# imu.net
KiCad netlist of a schematic drawn in Altium Designer
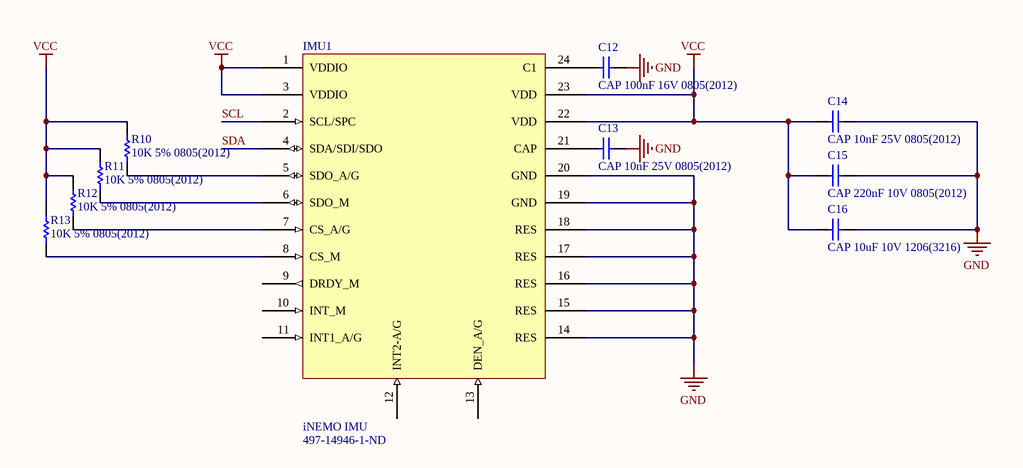
[diagram p0: imu.SchDoc]

(export (version "E")
  (design (tool "Eeschema 10.0.6"))
  (components
    (comp (ref "C12")
      (value "CAP 100nF 16V 0805(2012)")
      (footprint "CAPC0805(2012)145_M")
      (description "CAP 100nF 16V ±20% 0805 (2012 Metric) Thickness 1.45mm SMD")
      (fields (field (name "TOLERANCE") "Â±20%"))
      (libsource (lib "Altium Content Vault") (part "CAP"))
    )
    (comp (ref "C13")
      (value "CAP 10nF 25V 0805(2012)")
      (footprint "CAPC0805(2012)100_L")
      (description "CAP 10nF 25V ±2% 0805 (2012 Metric) Thickness 1mm SMD")
      (fields (field (name "TOLERANCE") "Â±2%"))
      (libsource (lib "Altium Content Vault") (part "CMP-1036-03826-1"))
    )
    (comp (ref "C14")
      (value "CAP 10nF 25V 0805(2012)")
      (footprint "CAPC0805(2012)100_L")
      (description "CAP 10nF 25V ±2% 0805 (2012 Metric) Thickness 1mm SMD")
      (fields (field (name "TOLERANCE") "Â±2%"))
      (libsource (lib "Altium Content Vault") (part "CMP-1036-03826-1"))
    )
    (comp (ref "C15")
      (value "CAP 220nF 10V 0805(2012)")
      (footprint "CAPC0805(2012)75_N")
      (description "CAP 220nF 10V ±20% 0805 (2012 Metric) Thickness 0.75mm SMD")
      (fields (field (name "TOLERANCE") "Â±20%"))
      (libsource (lib "Altium Content Vault") (part "CMP-1036-04526-1"))
    )
    (comp (ref "C16")
      (value "CAP 10uF 10V 1206(3216)")
      (footprint "CAPC1206(3216)130_L")
      (description "CAP 10uF 10V -20% to +80% 1206 (3216 Metric) Thickness 1.3mm SMD")
      (fields (field (name "TOLERANCE") "-20% to +80%"))
      (libsource (lib "Altium Content Vault") (part "CMP-1037-04970-1"))
    )
    (comp (ref "IMU1")
      (value "iNEMO IMU")
      (footprint "LGA-24")
      (fields (field (name "SUPPLIER PART NUMBER 1") "497-14946-1-ND"))
      (libsource (lib "lab4") (part "LSM9DS1"))
    )
    (comp (ref "R10")
      (value "10K 5% 0805(2012)")
      (footprint "RESC0805(2012)_L")
      (description "10K 0.125W 5% 0805 (2012 Metric)  SMD")
      (fields (field (name "POWER") "0.125 W") (field (name "TOLERANCE") "5 %"))
      (libsource (lib "Altium Content Vault") (part "CMP-1013-00098-1"))
    )
    (comp (ref "R11")
      (value "10K 5% 0805(2012)")
      (footprint "RESC0805(2012)_L")
      (description "10K 0.125W 5% 0805 (2012 Metric)  SMD")
      (fields (field (name "POWER") "0.125 W") (field (name "TOLERANCE") "5 %"))
      (libsource (lib "Altium Content Vault") (part "CMP-1013-00098-1"))
    )
    (comp (ref "R12")
      (value "10K 5% 0805(2012)")
      (footprint "RESC0805(2012)_L")
      (description "10K 0.125W 5% 0805 (2012 Metric)  SMD")
      (fields (field (name "POWER") "0.125 W") (field (name "TOLERANCE") "5 %"))
      (libsource (lib "Altium Content Vault") (part "CMP-1013-00098-1"))
    )
    (comp (ref "R13")
      (value "10K 5% 0805(2012)")
      (footprint "RESC0805(2012)_L")
      (description "10K 0.125W 5% 0805 (2012 Metric)  SMD")
      (fields (field (name "POWER") "0.125 W") (field (name "TOLERANCE") "5 %"))
      (libsource (lib "Altium Content Vault") (part "CMP-1013-00098-1"))
    )
  )
  (nets
    (net (code "1") (name "/SCL") (class "Default")
      (node (ref "IMU1") (pin "2") (pinfunction "SCL/SPC_2") (pintype "input"))
    )
    (net (code "2") (name "/SDA") (class "Default")
      (node (ref "IMU1") (pin "4") (pinfunction "SDA/SDI/SDO_4") (pintype "bidirectional"))
    )
    (net (code "3") (name "GND") (class "Default")
      (node (ref "C12") (pin "2") (pinfunction "2_2") (pintype "passive"))
      (node (ref "C13") (pin "2") (pinfunction "2_2") (pintype "passive"))
      (node (ref "C14") (pin "2") (pinfunction "2_2") (pintype "passive"))
      (node (ref "C15") (pin "1") (pinfunction "1_1") (pintype "passive"))
      (node (ref "C16") (pin "2") (pinfunction "2_2") (pintype "passive"))
      (node (ref "IMU1") (pin "14") (pinfunction "RES_14") (pintype "passive"))
      (node (ref "IMU1") (pin "15") (pinfunction "RES_15") (pintype "passive"))
      (node (ref "IMU1") (pin "16") (pinfunction "RES_16") (pintype "passive"))
      (node (ref "IMU1") (pin "17") (pinfunction "RES_17") (pintype "passive"))
      (node (ref "IMU1") (pin "18") (pinfunction "RES_18") (pintype "passive"))
      (node (ref "IMU1") (pin "19") (pinfunction "GND_19") (pintype "power_in"))
      (node (ref "IMU1") (pin "20") (pinfunction "GND_20") (pintype "power_in"))
    )
    (net (code "4") (name "Net-(IMU1-C1)") (class "Default")
      (node (ref "C12") (pin "1") (pinfunction "1_1") (pintype "passive"))
      (node (ref "IMU1") (pin "24") (pinfunction "C1_24") (pintype "passive"))
    )
    (net (code "5") (name "Net-(IMU1-CAP)") (class "Default")
      (node (ref "C13") (pin "1") (pinfunction "1_1") (pintype "passive"))
      (node (ref "IMU1") (pin "21") (pinfunction "CAP_21") (pintype "passive"))
    )
    (net (code "6") (name "Net-(IMU1-CS_A{slash}G)") (class "Default")
      (node (ref "IMU1") (pin "7") (pinfunction "CS_A/G_7") (pintype "input"))
      (node (ref "R12") (pin "1") (pinfunction "1_1") (pintype "passive"))
    )
    (net (code "7") (name "Net-(IMU1-CS_M)") (class "Default")
      (node (ref "IMU1") (pin "8") (pinfunction "CS_M_8") (pintype "input"))
      (node (ref "R13") (pin "1") (pinfunction "1_1") (pintype "passive"))
    )
    (net (code "8") (name "Net-(IMU1-SDO_A{slash}G)") (class "Default")
      (node (ref "IMU1") (pin "5") (pinfunction "SDO_A/G_5") (pintype "bidirectional"))
      (node (ref "R10") (pin "1") (pinfunction "1_1") (pintype "passive"))
    )
    (net (code "9") (name "Net-(IMU1-SDO_M)") (class "Default")
      (node (ref "IMU1") (pin "6") (pinfunction "SDO_M_6") (pintype "bidirectional"))
      (node (ref "R11") (pin "1") (pinfunction "1_1") (pintype "passive"))
    )
    (net (code "10") (name "VCC") (class "Default")
      (node (ref "C14") (pin "1") (pinfunction "1_1") (pintype "passive"))
      (node (ref "C15") (pin "2") (pinfunction "2_2") (pintype "passive"))
      (node (ref "C16") (pin "1") (pinfunction "1_1") (pintype "passive"))
      (node (ref "IMU1") (pin "1") (pinfunction "VDDIO_1") (pintype "power_in"))
      (node (ref "IMU1") (pin "22") (pinfunction "VDD_22") (pintype "power_in"))
      (node (ref "IMU1") (pin "23") (pinfunction "VDD_23") (pintype "power_in"))
      (node (ref "IMU1") (pin "3") (pinfunction "VDDIO_3") (pintype "power_in"))
      (node (ref "R10") (pin "2") (pinfunction "2_2") (pintype "passive"))
      (node (ref "R11") (pin "2") (pinfunction "2_2") (pintype "passive"))
      (node (ref "R12") (pin "2") (pinfunction "2_2") (pintype "passive"))
      (node (ref "R13") (pin "2") (pinfunction "2_2") (pintype "passive"))
    )
    (net (code "11") (name "unconnected-(IMU1-DEN_A{slash}G-Pad13)") (class "Default")
      (node (ref "IMU1") (pin "13") (pinfunction "DEN_A/G_13") (pintype "input"))
    )
    (net (code "12") (name "unconnected-(IMU1-DRDY_M-Pad9)") (class "Default")
      (node (ref "IMU1") (pin "9") (pinfunction "DRDY_M_9") (pintype "output"))
    )
    (net (code "13") (name "unconnected-(IMU1-INT1_A{slash}G-Pad11)") (class "Default")
      (node (ref "IMU1") (pin "11") (pinfunction "INT1_A/G_11") (pintype "input"))
    )
    (net (code "14") (name "unconnected-(IMU1-INT2-A{slash}G-Pad12)") (class "Default")
      (node (ref "IMU1") (pin "12") (pinfunction "INT2-A/G_12") (pintype "input"))
    )
    (net (code "15") (name "unconnected-(IMU1-INT_M-Pad10)") (class "Default")
      (node (ref "IMU1") (pin "10") (pinfunction "INT_M_10") (pintype "input"))
    )
  )
)
